# LoadCell_Driver.net
KiCad netlist of a schematic drawn in Altium Designer
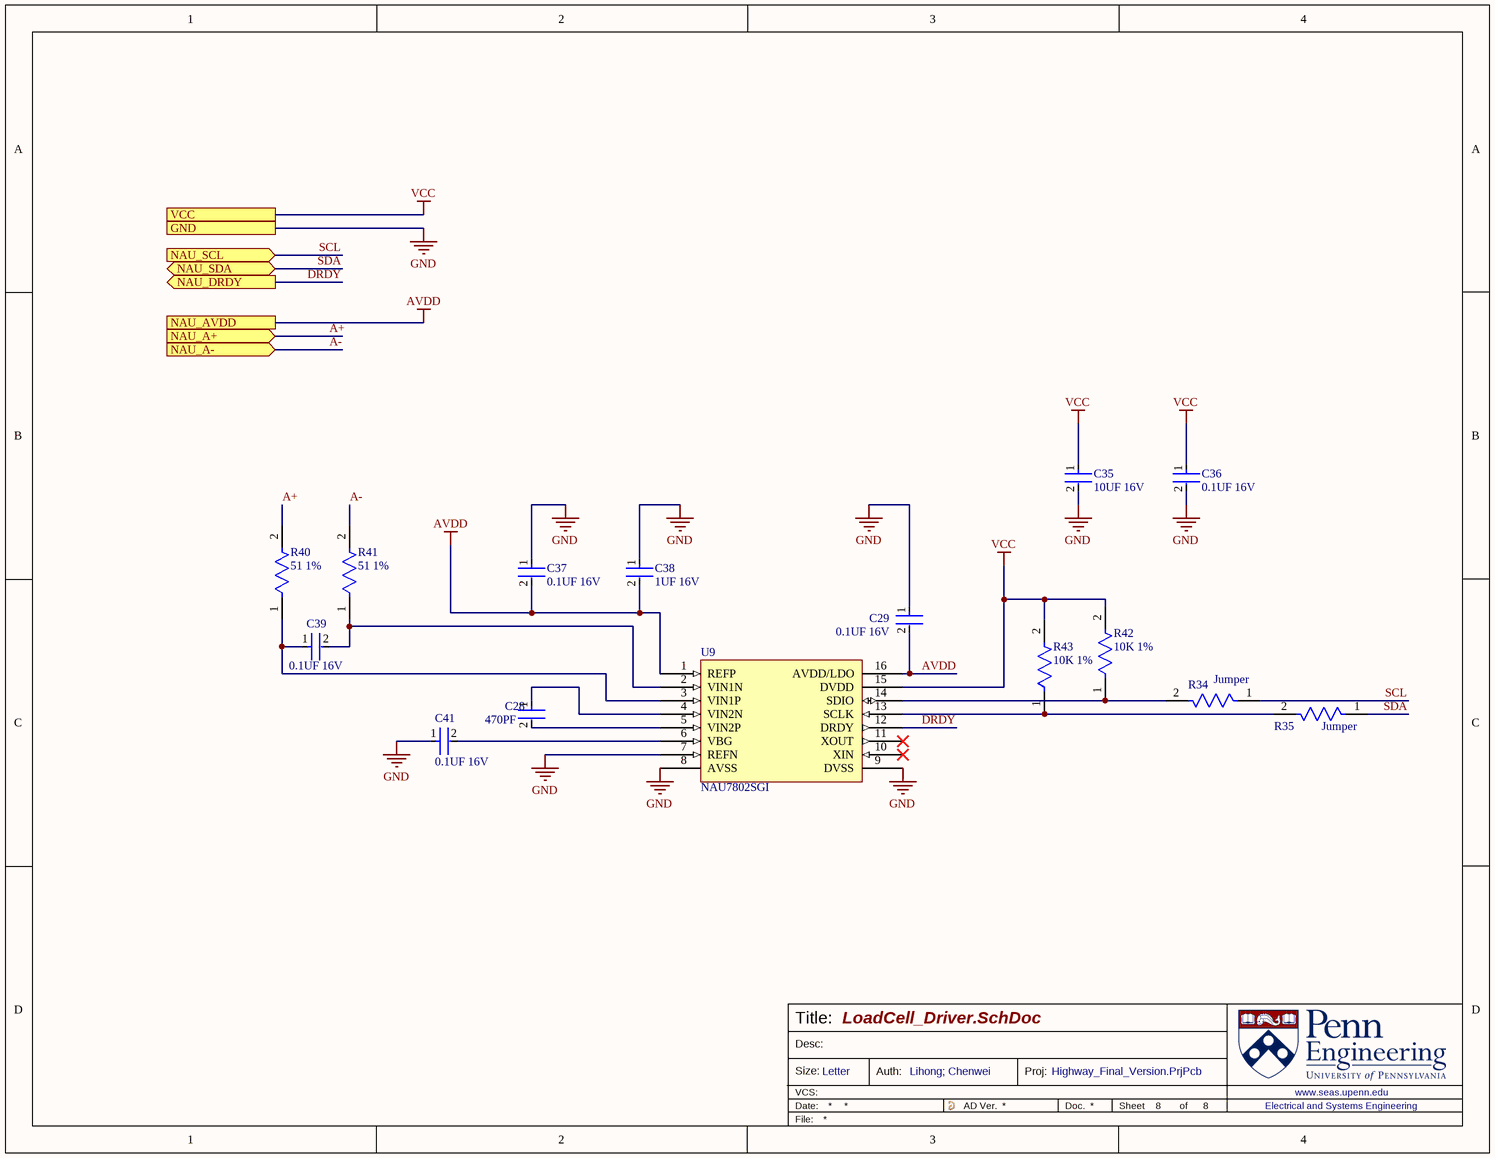
[diagram p0: LoadCell_Driver.SchDoc]

(export (version "E")
  (design (tool "Eeschema 10.0.6"))
  (components
    (comp (ref "C28")
      (value "470PF")
      (footprint "FP-0402-L_1_0_1-W_0_5_0_1-IPC_A")
      (description "General Purpose Ceramic Capacitor, 0402, 470pF, 10%, X7R, 15%, 50V")
      (fields (field (name "TOLERANCE") "10%") (field (name "VOLTAGE") "50V"))
      (libsource (lib "Altium Content Vault") (part "b4654b650e69147ec39a6b967a45e02"))
    )
    (comp (ref "C29")
      (value "0.1UF 16V")
      (footprint "FP-CC0402-MFG")
      (description "CC0402 100 nF X7R 10.00% 25 V")
      (fields
        (field (name "MANUFACTURER PART NUMBER") "CC0402KPX7R8BB104")
        (field (name "MANUFACTURER") "YAGEO")
      )
      (libsource (lib "Altium Content Vault") (part "11868f565c42a9108669ba33697ecf6"))
    )
    (comp (ref "C35")
      (value "10UF 16V")
      (footprint "FP-CC0603-DB-MFG")
      (description "CAP CER 10UF 6.3V X5R 0603")
      (fields (field (name "TOLERANCE") "20%"))
      (libsource (lib "Altium Content Vault") (part "e9c51b7dd13d4faca003ae77663ab08"))
    )
    (comp (ref "C36")
      (value "0.1UF 16V")
      (footprint "FP-CC0402-MFG")
      (description "CC0402 100 nF X7R 10.00% 25 V")
      (fields
        (field (name "MANUFACTURER PART NUMBER") "CC0402KPX7R8BB104")
        (field (name "MANUFACTURER") "YAGEO")
      )
      (libsource (lib "Altium Content Vault") (part "11868f565c42a9108669ba33697ecf6"))
    )
    (comp (ref "C37")
      (value "0.1UF 16V")
      (footprint "FP-CC0402-MFG")
      (description "CC0402 100 nF X7R 10.00% 25 V")
      (fields
        (field (name "MANUFACTURER PART NUMBER") "CC0402KPX7R8BB104")
        (field (name "MANUFACTURER") "YAGEO")
      )
      (libsource (lib "Altium Content Vault") (part "11868f565c42a9108669ba33697ecf6"))
    )
    (comp (ref "C38")
      (value "1UF 16V")
      (footprint "FP-CC0603-DA-MFG")
      (description "CC0603 1 uF X7R 10.00% 16 V")
      (fields (field (name "MANUFACTURER") "YAGEO") (field (name "TOLERANCE") "0.1"))
      (libsource (lib "Altium Content Vault") (part "11868f565c42a9108669ba33697ecf6"))
    )
    (comp (ref "C39")
      (value "0.1UF 16V")
      (footprint "FP-CC0402-MFG")
      (description "CC0402 100 nF X7R 10.00% 25 V")
      (fields
        (field (name "MANUFACTURER PART NUMBER") "CC0402KPX7R8BB104")
        (field (name "MANUFACTURER") "YAGEO")
      )
      (libsource (lib "Altium Content Vault") (part "11868f565c42a9108669ba33697ecf6"))
    )
    (comp (ref "C41")
      (value "0.1UF 16V")
      (footprint "FP-CC0402-MFG")
      (description "CC0402 100 nF X7R 10.00% 25 V")
      (fields
        (field (name "MANUFACTURER PART NUMBER") "CC0402KPX7R8BB104")
        (field (name "MANUFACTURER") "YAGEO")
      )
      (libsource (lib "Altium Content Vault") (part "11868f565c42a9108669ba33697ecf6"))
    )
    (comp (ref "R34")
      (value "Jumper")
      (footprint "FP-RMCF0603-MFG")
      (description "RES 0 OHM JUMPER 1/10W 0603")
      (fields
        (field (name "MANUFACTURER PART NUMBER") "RMCF0603ZT0R00")
        (field (name "OCTOPART") "https://octopart.com/rmcf0603zt0r00-stackpole+electronics-19213618")
      )
      (libsource (lib "Altium Content Vault") (part "1029c3af85768c4190bb7ad29bc67b5"))
    )
    (comp (ref "R35")
      (value "Jumper")
      (footprint "FP-RMCF0603-MFG")
      (description "RES 0 OHM JUMPER 1/10W 0603")
      (fields
        (field (name "MANUFACTURER PART NUMBER") "RMCF0603ZT0R00")
        (field (name "OCTOPART") "https://octopart.com/rmcf0603zt0r00-stackpole+electronics-19213618")
      )
      (libsource (lib "Altium Content Vault") (part "1029c3af85768c4190bb7ad29bc67b5"))
    )
    (comp (ref "R40")
      (value "51 1%")
      (footprint "FP-RMCF0402-IPC_C")
      (description "51Ω ±1% 0.063W 0402 Thick Film Chip Resistor AEC-Q200 compliant")
      (fields (field (name "TOLERANCE") "1%"))
      (libsource (lib "Altium Content Vault") (part "1029c3af85768c4190bb7ad29bc67b5"))
    )
    (comp (ref "R41")
      (value "51 1%")
      (footprint "FP-RMCF0402-IPC_C")
      (description "51Ω ±1% 0.063W 0402 Thick Film Chip Resistor AEC-Q200 compliant")
      (fields (field (name "TOLERANCE") "1%"))
      (libsource (lib "Altium Content Vault") (part "1029c3af85768c4190bb7ad29bc67b5"))
    )
    (comp (ref "R42")
      (value "10K 1%")
      (footprint "FP-RNCP0603-IPC_A")
      (description "10kΩ ±1% 0.125W 0603 High Power Anti-Sulfur Thin Film Chip Resistor")
      (fields (field (name "TOLERANCE") "1%"))
      (libsource (lib "Altium Content Vault") (part "1029c3af85768c4190bb7ad29bc67b5"))
    )
    (comp (ref "R43")
      (value "10K 1%")
      (footprint "FP-RNCP0603-IPC_A")
      (description "10kΩ ±1% 0.125W 0603 High Power Anti-Sulfur Thin Film Chip Resistor")
      (fields (field (name "TOLERANCE") "1%"))
      (libsource (lib "Altium Content Vault") (part "1029c3af85768c4190bb7ad29bc67b5"))
    )
    (comp (ref "U9")
      (value "NAU7802SGI")
      (footprint "SOP127P600X175-16N")
      (description "ADC, Delta-Sigma, 24-Bit, 1 Func, 2 Channel, Serial Access, PDSO16")
      (libsource (lib "University of Pennsylvania (ESE Labs)") (part "NAU7802SGI-Symbol-1"))
    )
  )
  (nets
    (net (code "1") (name "/A+") (class "Default")
      (node (ref "R40") (pin "2") (pinfunction "2_2") (pintype "passive"))
    )
    (net (code "2") (name "/A-") (class "Default")
      (node (ref "R41") (pin "2") (pinfunction "2_2") (pintype "passive"))
    )
    (net (code "3") (name "/DRDY") (class "Default")
      (node (ref "U9") (pin "12") (pinfunction "DRDY_12") (pintype "output"))
    )
    (net (code "4") (name "/SCL") (class "Default")
      (node (ref "R34") (pin "1") (pinfunction "1_1") (pintype "passive"))
    )
    (net (code "5") (name "/SDA") (class "Default")
      (node (ref "R35") (pin "1") (pinfunction "1_1") (pintype "passive"))
    )
    (net (code "6") (name "AVDD") (class "Default")
      (node (ref "C29") (pin "2") (pinfunction "2_2") (pintype "passive"))
      (node (ref "C37") (pin "2") (pinfunction "2_2") (pintype "passive"))
      (node (ref "C38") (pin "2") (pinfunction "2_2") (pintype "passive"))
      (node (ref "U9") (pin "1") (pinfunction "REFP_1") (pintype "input"))
      (node (ref "U9") (pin "16") (pinfunction "AVDD/LDO_16") (pintype "power_in"))
    )
    (net (code "7") (name "GND") (class "Default")
      (node (ref "C29") (pin "1") (pinfunction "1_1") (pintype "passive"))
      (node (ref "C35") (pin "2") (pinfunction "2_2") (pintype "passive"))
      (node (ref "C36") (pin "2") (pinfunction "2_2") (pintype "passive"))
      (node (ref "C37") (pin "1") (pinfunction "1_1") (pintype "passive"))
      (node (ref "C38") (pin "1") (pinfunction "1_1") (pintype "passive"))
      (node (ref "C41") (pin "1") (pinfunction "1_1") (pintype "passive"))
      (node (ref "U9") (pin "7") (pinfunction "REFN_7") (pintype "input"))
      (node (ref "U9") (pin "8") (pinfunction "AVSS_8") (pintype "power_in"))
      (node (ref "U9") (pin "9") (pinfunction "DVSS_9") (pintype "power_in"))
    )
    (net (code "8") (name "Net-(U9-SCLK)") (class "Default")
      (node (ref "R35") (pin "2") (pinfunction "2_2") (pintype "passive"))
      (node (ref "R43") (pin "1") (pinfunction "1_1") (pintype "passive"))
      (node (ref "U9") (pin "13") (pinfunction "SCLK_13") (pintype "input"))
    )
    (net (code "9") (name "Net-(U9-SDIO)") (class "Default")
      (node (ref "R34") (pin "2") (pinfunction "2_2") (pintype "passive"))
      (node (ref "R42") (pin "1") (pinfunction "1_1") (pintype "passive"))
      (node (ref "U9") (pin "14") (pinfunction "SDIO_14") (pintype "bidirectional"))
    )
    (net (code "10") (name "Net-(U9-VBG)") (class "Default")
      (node (ref "C41") (pin "2") (pinfunction "2_2") (pintype "passive"))
      (node (ref "U9") (pin "6") (pinfunction "VBG_6") (pintype "input"))
    )
    (net (code "11") (name "Net-(U9-VIN1N)") (class "Default")
      (node (ref "C39") (pin "2") (pinfunction "2_2") (pintype "passive"))
      (node (ref "R41") (pin "1") (pinfunction "1_1") (pintype "passive"))
      (node (ref "U9") (pin "2") (pinfunction "VIN1N_2") (pintype "input"))
    )
    (net (code "12") (name "Net-(U9-VIN1P)") (class "Default")
      (node (ref "C39") (pin "1") (pinfunction "1_1") (pintype "passive"))
      (node (ref "R40") (pin "1") (pinfunction "1_1") (pintype "passive"))
      (node (ref "U9") (pin "3") (pinfunction "VIN1P_3") (pintype "input"))
    )
    (net (code "13") (name "Net-(U9-VIN2N)") (class "Default")
      (node (ref "C28") (pin "1") (pinfunction "1_1") (pintype "passive"))
      (node (ref "U9") (pin "4") (pinfunction "VIN2N_4") (pintype "input"))
    )
    (net (code "14") (name "Net-(U9-VIN2P)") (class "Default")
      (node (ref "C28") (pin "2") (pinfunction "2_2") (pintype "passive"))
      (node (ref "U9") (pin "5") (pinfunction "VIN2P_5") (pintype "input"))
    )
    (net (code "15") (name "VCC") (class "Default")
      (node (ref "C35") (pin "1") (pinfunction "1_1") (pintype "passive"))
      (node (ref "C36") (pin "1") (pinfunction "1_1") (pintype "passive"))
      (node (ref "R42") (pin "2") (pinfunction "2_2") (pintype "passive"))
      (node (ref "R43") (pin "2") (pinfunction "2_2") (pintype "passive"))
      (node (ref "U9") (pin "15") (pinfunction "DVDD_15") (pintype "power_in"))
    )
    (net (code "16") (name "unconnected-(U9-XIN-Pad10)") (class "Default")
      (node (ref "U9") (pin "10") (pinfunction "XIN_10") (pintype "input+no_connect"))
    )
    (net (code "17") (name "unconnected-(U9-XOUT-Pad11)") (class "Default")
      (node (ref "U9") (pin "11") (pinfunction "XOUT_11") (pintype "output+no_connect"))
    )
  )
)
